# LEDChain1.net
KiCad netlist of a schematic drawn in Altium Designer
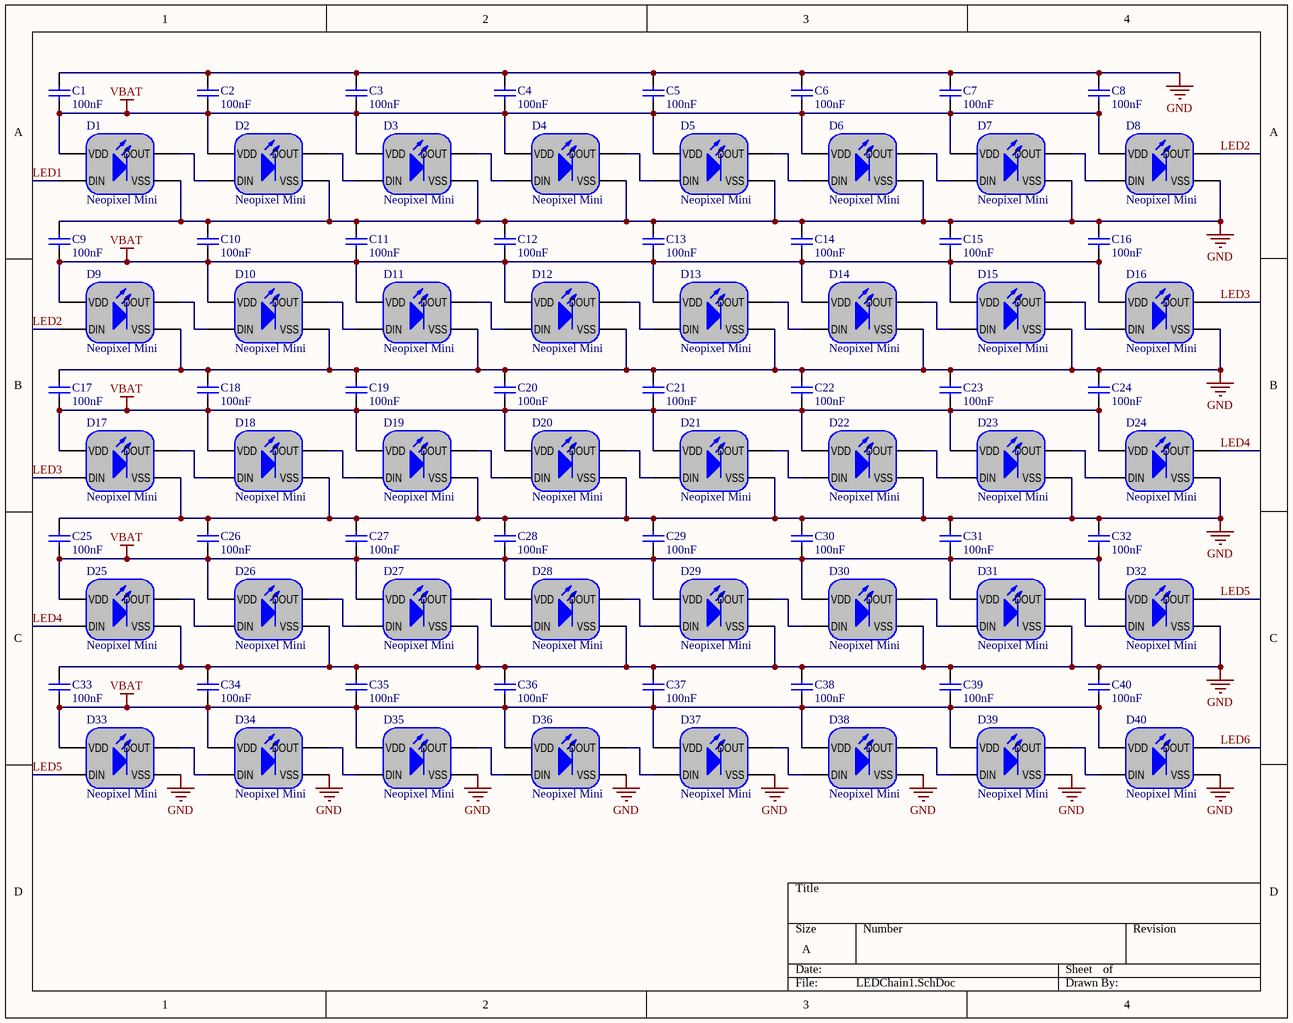
[diagram p0: LEDChain1.SchDoc]

(export (version "E")
  (design (tool "Eeschema 10.0.6"))
  (components
    (comp (ref "C1")
      (value "100nF")
      (footprint "0402_CAP")
      (description "CAP CER 0.1UF 16V X7R 0402")
      (fields (field (name "PUBLISHER") "Altium Limited"))
      (libsource (lib "Common Passives") (part "CAP_100N_0603"))
    )
    (comp (ref "C2")
      (value "100nF")
      (footprint "0402_CAP")
      (description "CAP CER 0.1UF 16V X7R 0402")
      (fields (field (name "PUBLISHER") "Altium Limited"))
      (libsource (lib "Common Passives") (part "CAP_100N_0603"))
    )
    (comp (ref "C3")
      (value "100nF")
      (footprint "0402_CAP")
      (description "CAP CER 0.1UF 16V X7R 0402")
      (fields (field (name "PUBLISHER") "Altium Limited"))
      (libsource (lib "Common Passives") (part "CAP_100N_0603"))
    )
    (comp (ref "C4")
      (value "100nF")
      (footprint "0402_CAP")
      (description "CAP CER 0.1UF 16V X7R 0402")
      (fields (field (name "PUBLISHER") "Altium Limited"))
      (libsource (lib "Common Passives") (part "CAP_100N_0603"))
    )
    (comp (ref "C5")
      (value "100nF")
      (footprint "0402_CAP")
      (description "CAP CER 0.1UF 16V X7R 0402")
      (fields (field (name "PUBLISHER") "Altium Limited"))
      (libsource (lib "Common Passives") (part "CAP_100N_0603"))
    )
    (comp (ref "C6")
      (value "100nF")
      (footprint "0402_CAP")
      (description "CAP CER 0.1UF 16V X7R 0402")
      (fields (field (name "PUBLISHER") "Altium Limited"))
      (libsource (lib "Common Passives") (part "CAP_100N_0603"))
    )
    (comp (ref "C7")
      (value "100nF")
      (footprint "0402_CAP")
      (description "CAP CER 0.1UF 16V X7R 0402")
      (fields (field (name "PUBLISHER") "Altium Limited"))
      (libsource (lib "Common Passives") (part "CAP_100N_0603"))
    )
    (comp (ref "C8")
      (value "100nF")
      (footprint "0402_CAP")
      (description "CAP CER 0.1UF 16V X7R 0402")
      (fields (field (name "PUBLISHER") "Altium Limited"))
      (libsource (lib "Common Passives") (part "CAP_100N_0603"))
    )
    (comp (ref "C9")
      (value "100nF")
      (footprint "0402_CAP")
      (description "CAP CER 0.1UF 16V X7R 0402")
      (fields (field (name "PUBLISHER") "Altium Limited"))
      (libsource (lib "Common Passives") (part "CAP_100N_0603"))
    )
    (comp (ref "C10")
      (value "100nF")
      (footprint "0402_CAP")
      (description "CAP CER 0.1UF 16V X7R 0402")
      (fields (field (name "PUBLISHER") "Altium Limited"))
      (libsource (lib "Common Passives") (part "CAP_100N_0603"))
    )
    (comp (ref "C11")
      (value "100nF")
      (footprint "0402_CAP")
      (description "CAP CER 0.1UF 16V X7R 0402")
      (fields (field (name "PUBLISHER") "Altium Limited"))
      (libsource (lib "Common Passives") (part "CAP_100N_0603"))
    )
    (comp (ref "C12")
      (value "100nF")
      (footprint "0402_CAP")
      (description "CAP CER 0.1UF 16V X7R 0402")
      (fields (field (name "PUBLISHER") "Altium Limited"))
      (libsource (lib "Common Passives") (part "CAP_100N_0603"))
    )
    (comp (ref "C13")
      (value "100nF")
      (footprint "0402_CAP")
      (description "CAP CER 0.1UF 16V X7R 0402")
      (fields (field (name "PUBLISHER") "Altium Limited"))
      (libsource (lib "Common Passives") (part "CAP_100N_0603"))
    )
    (comp (ref "C14")
      (value "100nF")
      (footprint "0402_CAP")
      (description "CAP CER 0.1UF 16V X7R 0402")
      (fields (field (name "PUBLISHER") "Altium Limited"))
      (libsource (lib "Common Passives") (part "CAP_100N_0603"))
    )
    (comp (ref "C15")
      (value "100nF")
      (footprint "0402_CAP")
      (description "CAP CER 0.1UF 16V X7R 0402")
      (fields (field (name "PUBLISHER") "Altium Limited"))
      (libsource (lib "Common Passives") (part "CAP_100N_0603"))
    )
    (comp (ref "C16")
      (value "100nF")
      (footprint "0402_CAP")
      (description "CAP CER 0.1UF 16V X7R 0402")
      (fields (field (name "PUBLISHER") "Altium Limited"))
      (libsource (lib "Common Passives") (part "CAP_100N_0603"))
    )
    (comp (ref "C17")
      (value "100nF")
      (footprint "0402_CAP")
      (description "CAP CER 0.1UF 16V X7R 0402")
      (fields (field (name "PUBLISHER") "Altium Limited"))
      (libsource (lib "Common Passives") (part "CAP_100N_0603"))
    )
    (comp (ref "C18")
      (value "100nF")
      (footprint "0402_CAP")
      (description "CAP CER 0.1UF 16V X7R 0402")
      (fields (field (name "PUBLISHER") "Altium Limited"))
      (libsource (lib "Common Passives") (part "CAP_100N_0603"))
    )
    (comp (ref "C19")
      (value "100nF")
      (footprint "0402_CAP")
      (description "CAP CER 0.1UF 16V X7R 0402")
      (fields (field (name "PUBLISHER") "Altium Limited"))
      (libsource (lib "Common Passives") (part "CAP_100N_0603"))
    )
    (comp (ref "C20")
      (value "100nF")
      (footprint "0402_CAP")
      (description "CAP CER 0.1UF 16V X7R 0402")
      (fields (field (name "PUBLISHER") "Altium Limited"))
      (libsource (lib "Common Passives") (part "CAP_100N_0603"))
    )
    (comp (ref "C21")
      (value "100nF")
      (footprint "0402_CAP")
      (description "CAP CER 0.1UF 16V X7R 0402")
      (fields (field (name "PUBLISHER") "Altium Limited"))
      (libsource (lib "Common Passives") (part "CAP_100N_0603"))
    )
    (comp (ref "C22")
      (value "100nF")
      (footprint "0402_CAP")
      (description "CAP CER 0.1UF 16V X7R 0402")
      (fields (field (name "PUBLISHER") "Altium Limited"))
      (libsource (lib "Common Passives") (part "CAP_100N_0603"))
    )
    (comp (ref "C23")
      (value "100nF")
      (footprint "0402_CAP")
      (description "CAP CER 0.1UF 16V X7R 0402")
      (fields (field (name "PUBLISHER") "Altium Limited"))
      (libsource (lib "Common Passives") (part "CAP_100N_0603"))
    )
    (comp (ref "C24")
      (value "100nF")
      (footprint "0402_CAP")
      (description "CAP CER 0.1UF 16V X7R 0402")
      (fields (field (name "PUBLISHER") "Altium Limited"))
      (libsource (lib "Common Passives") (part "CAP_100N_0603"))
    )
    (comp (ref "C25")
      (value "100nF")
      (footprint "0402_CAP")
      (description "CAP CER 0.1UF 16V X7R 0402")
      (fields (field (name "PUBLISHER") "Altium Limited"))
      (libsource (lib "Common Passives") (part "CAP_100N_0603"))
    )
    (comp (ref "C26")
      (value "100nF")
      (footprint "0402_CAP")
      (description "CAP CER 0.1UF 16V X7R 0402")
      (fields (field (name "PUBLISHER") "Altium Limited"))
      (libsource (lib "Common Passives") (part "CAP_100N_0603"))
    )
    (comp (ref "C27")
      (value "100nF")
      (footprint "0402_CAP")
      (description "CAP CER 0.1UF 16V X7R 0402")
      (fields (field (name "PUBLISHER") "Altium Limited"))
      (libsource (lib "Common Passives") (part "CAP_100N_0603"))
    )
    (comp (ref "C28")
      (value "100nF")
      (footprint "0402_CAP")
      (description "CAP CER 0.1UF 16V X7R 0402")
      (fields (field (name "PUBLISHER") "Altium Limited"))
      (libsource (lib "Common Passives") (part "CAP_100N_0603"))
    )
    (comp (ref "C29")
      (value "100nF")
      (footprint "0402_CAP")
      (description "CAP CER 0.1UF 16V X7R 0402")
      (fields (field (name "PUBLISHER") "Altium Limited"))
      (libsource (lib "Common Passives") (part "CAP_100N_0603"))
    )
    (comp (ref "C30")
      (value "100nF")
      (footprint "0402_CAP")
      (description "CAP CER 0.1UF 16V X7R 0402")
      (fields (field (name "PUBLISHER") "Altium Limited"))
      (libsource (lib "Common Passives") (part "CAP_100N_0603"))
    )
    (comp (ref "C31")
      (value "100nF")
      (footprint "0402_CAP")
      (description "CAP CER 0.1UF 16V X7R 0402")
      (fields (field (name "PUBLISHER") "Altium Limited"))
      (libsource (lib "Common Passives") (part "CAP_100N_0603"))
    )
    (comp (ref "C32")
      (value "100nF")
      (footprint "0402_CAP")
      (description "CAP CER 0.1UF 16V X7R 0402")
      (fields (field (name "PUBLISHER") "Altium Limited"))
      (libsource (lib "Common Passives") (part "CAP_100N_0603"))
    )
    (comp (ref "C33")
      (value "100nF")
      (footprint "0402_CAP")
      (description "CAP CER 0.1UF 16V X7R 0402")
      (fields (field (name "PUBLISHER") "Altium Limited"))
      (libsource (lib "Common Passives") (part "CAP_100N_0603"))
    )
    (comp (ref "C34")
      (value "100nF")
      (footprint "0402_CAP")
      (description "CAP CER 0.1UF 16V X7R 0402")
      (fields (field (name "PUBLISHER") "Altium Limited"))
      (libsource (lib "Common Passives") (part "CAP_100N_0603"))
    )
    (comp (ref "C35")
      (value "100nF")
      (footprint "0402_CAP")
      (description "CAP CER 0.1UF 16V X7R 0402")
      (fields (field (name "PUBLISHER") "Altium Limited"))
      (libsource (lib "Common Passives") (part "CAP_100N_0603"))
    )
    (comp (ref "C36")
      (value "100nF")
      (footprint "0402_CAP")
      (description "CAP CER 0.1UF 16V X7R 0402")
      (fields (field (name "PUBLISHER") "Altium Limited"))
      (libsource (lib "Common Passives") (part "CAP_100N_0603"))
    )
    (comp (ref "C37")
      (value "100nF")
      (footprint "0402_CAP")
      (description "CAP CER 0.1UF 16V X7R 0402")
      (fields (field (name "PUBLISHER") "Altium Limited"))
      (libsource (lib "Common Passives") (part "CAP_100N_0603"))
    )
    (comp (ref "C38")
      (value "100nF")
      (footprint "0402_CAP")
      (description "CAP CER 0.1UF 16V X7R 0402")
      (fields (field (name "PUBLISHER") "Altium Limited"))
      (libsource (lib "Common Passives") (part "CAP_100N_0603"))
    )
    (comp (ref "C39")
      (value "100nF")
      (footprint "0402_CAP")
      (description "CAP CER 0.1UF 16V X7R 0402")
      (fields (field (name "PUBLISHER") "Altium Limited"))
      (libsource (lib "Common Passives") (part "CAP_100N_0603"))
    )
    (comp (ref "C40")
      (value "100nF")
      (footprint "0402_CAP")
      (description "CAP CER 0.1UF 16V X7R 0402")
      (fields (field (name "PUBLISHER") "Altium Limited"))
      (libsource (lib "Common Passives") (part "CAP_100N_0603"))
    )
    (comp (ref "D1")
      (value "Neopixel Mini")
      (footprint "SK6812 (3535)")
      (description "ADDRESS LED DISC SERIAL RGB")
      (libsource (lib "Diodes") (part "SK6812MINI-B-001"))
    )
    (comp (ref "D2")
      (value "Neopixel Mini")
      (footprint "SK6812 (3535)")
      (description "ADDRESS LED DISC SERIAL RGB")
      (libsource (lib "Diodes") (part "SK6812MINI-B-001"))
    )
    (comp (ref "D3")
      (value "Neopixel Mini")
      (footprint "SK6812 (3535)")
      (description "ADDRESS LED DISC SERIAL RGB")
      (libsource (lib "Diodes") (part "SK6812MINI-B-001"))
    )
    (comp (ref "D4")
      (value "Neopixel Mini")
      (footprint "SK6812 (3535)")
      (description "ADDRESS LED DISC SERIAL RGB")
      (libsource (lib "Diodes") (part "SK6812MINI-B-001"))
    )
    (comp (ref "D5")
      (value "Neopixel Mini")
      (footprint "SK6812 (3535)")
      (description "ADDRESS LED DISC SERIAL RGB")
      (libsource (lib "Diodes") (part "SK6812MINI-B-001"))
    )
    (comp (ref "D6")
      (value "Neopixel Mini")
      (footprint "SK6812 (3535)")
      (description "ADDRESS LED DISC SERIAL RGB")
      (libsource (lib "Diodes") (part "SK6812MINI-B-001"))
    )
    (comp (ref "D7")
      (value "Neopixel Mini")
      (footprint "SK6812 (3535)")
      (description "ADDRESS LED DISC SERIAL RGB")
      (libsource (lib "Diodes") (part "SK6812MINI-B-001"))
    )
    (comp (ref "D8")
      (value "Neopixel Mini")
      (footprint "SK6812 (3535)")
      (description "ADDRESS LED DISC SERIAL RGB")
      (libsource (lib "Diodes") (part "SK6812MINI-B-001"))
    )
    (comp (ref "D9")
      (value "Neopixel Mini")
      (footprint "SK6812 (3535)")
      (description "ADDRESS LED DISC SERIAL RGB")
      (libsource (lib "Diodes") (part "SK6812MINI-B-001"))
    )
    (comp (ref "D10")
      (value "Neopixel Mini")
      (footprint "SK6812 (3535)")
      (description "ADDRESS LED DISC SERIAL RGB")
      (libsource (lib "Diodes") (part "SK6812MINI-B-001"))
    )
    (comp (ref "D11")
      (value "Neopixel Mini")
      (footprint "SK6812 (3535)")
      (description "ADDRESS LED DISC SERIAL RGB")
      (libsource (lib "Diodes") (part "SK6812MINI-B-001"))
    )
    (comp (ref "D12")
      (value "Neopixel Mini")
      (footprint "SK6812 (3535)")
      (description "ADDRESS LED DISC SERIAL RGB")
      (libsource (lib "Diodes") (part "SK6812MINI-B-001"))
    )
    (comp (ref "D13")
      (value "Neopixel Mini")
      (footprint "SK6812 (3535)")
      (description "ADDRESS LED DISC SERIAL RGB")
      (libsource (lib "Diodes") (part "SK6812MINI-B-001"))
    )
    (comp (ref "D14")
      (value "Neopixel Mini")
      (footprint "SK6812 (3535)")
      (description "ADDRESS LED DISC SERIAL RGB")
      (libsource (lib "Diodes") (part "SK6812MINI-B-001"))
    )
    (comp (ref "D15")
      (value "Neopixel Mini")
      (footprint "SK6812 (3535)")
      (description "ADDRESS LED DISC SERIAL RGB")
      (libsource (lib "Diodes") (part "SK6812MINI-B-001"))
    )
    (comp (ref "D16")
      (value "Neopixel Mini")
      (footprint "SK6812 (3535)")
      (description "ADDRESS LED DISC SERIAL RGB")
      (libsource (lib "Diodes") (part "SK6812MINI-B-001"))
    )
    (comp (ref "D17")
      (value "Neopixel Mini")
      (footprint "SK6812 (3535)")
      (description "ADDRESS LED DISC SERIAL RGB")
      (libsource (lib "Diodes") (part "SK6812MINI-B-001"))
    )
    (comp (ref "D18")
      (value "Neopixel Mini")
      (footprint "SK6812 (3535)")
      (description "ADDRESS LED DISC SERIAL RGB")
      (libsource (lib "Diodes") (part "SK6812MINI-B-001"))
    )
    (comp (ref "D19")
      (value "Neopixel Mini")
      (footprint "SK6812 (3535)")
      (description "ADDRESS LED DISC SERIAL RGB")
      (libsource (lib "Diodes") (part "SK6812MINI-B-001"))
    )
    (comp (ref "D20")
      (value "Neopixel Mini")
      (footprint "SK6812 (3535)")
      (description "ADDRESS LED DISC SERIAL RGB")
      (libsource (lib "Diodes") (part "SK6812MINI-B-001"))
    )
    (comp (ref "D21")
      (value "Neopixel Mini")
      (footprint "SK6812 (3535)")
      (description "ADDRESS LED DISC SERIAL RGB")
      (libsource (lib "Diodes") (part "SK6812MINI-B-001"))
    )
    (comp (ref "D22")
      (value "Neopixel Mini")
      (footprint "SK6812 (3535)")
      (description "ADDRESS LED DISC SERIAL RGB")
      (libsource (lib "Diodes") (part "SK6812MINI-B-001"))
    )
    (comp (ref "D23")
      (value "Neopixel Mini")
      (footprint "SK6812 (3535)")
      (description "ADDRESS LED DISC SERIAL RGB")
      (libsource (lib "Diodes") (part "SK6812MINI-B-001"))
    )
    (comp (ref "D24")
      (value "Neopixel Mini")
      (footprint "SK6812 (3535)")
      (description "ADDRESS LED DISC SERIAL RGB")
      (libsource (lib "Diodes") (part "SK6812MINI-B-001"))
    )
    (comp (ref "D25")
      (value "Neopixel Mini")
      (footprint "SK6812 (3535)")
      (description "ADDRESS LED DISC SERIAL RGB")
      (libsource (lib "Diodes") (part "SK6812MINI-B-001"))
    )
    (comp (ref "D26")
      (value "Neopixel Mini")
      (footprint "SK6812 (3535)")
      (description "ADDRESS LED DISC SERIAL RGB")
      (libsource (lib "Diodes") (part "SK6812MINI-B-001"))
    )
    (comp (ref "D27")
      (value "Neopixel Mini")
      (footprint "SK6812 (3535)")
      (description "ADDRESS LED DISC SERIAL RGB")
      (libsource (lib "Diodes") (part "SK6812MINI-B-001"))
    )
    (comp (ref "D28")
      (value "Neopixel Mini")
      (footprint "SK6812 (3535)")
      (description "ADDRESS LED DISC SERIAL RGB")
      (libsource (lib "Diodes") (part "SK6812MINI-B-001"))
    )
    (comp (ref "D29")
      (value "Neopixel Mini")
      (footprint "SK6812 (3535)")
      (description "ADDRESS LED DISC SERIAL RGB")
      (libsource (lib "Diodes") (part "SK6812MINI-B-001"))
    )
    (comp (ref "D30")
      (value "Neopixel Mini")
      (footprint "SK6812 (3535)")
      (description "ADDRESS LED DISC SERIAL RGB")
      (libsource (lib "Diodes") (part "SK6812MINI-B-001"))
    )
    (comp (ref "D31")
      (value "Neopixel Mini")
      (footprint "SK6812 (3535)")
      (description "ADDRESS LED DISC SERIAL RGB")
      (libsource (lib "Diodes") (part "SK6812MINI-B-001"))
    )
    (comp (ref "D32")
      (value "Neopixel Mini")
      (footprint "SK6812 (3535)")
      (description "ADDRESS LED DISC SERIAL RGB")
      (libsource (lib "Diodes") (part "SK6812MINI-B-001"))
    )
    (comp (ref "D33")
      (value "Neopixel Mini")
      (footprint "SK6812 (3535)")
      (description "ADDRESS LED DISC SERIAL RGB")
      (libsource (lib "Diodes") (part "SK6812MINI-B-001"))
    )
    (comp (ref "D34")
      (value "Neopixel Mini")
      (footprint "SK6812 (3535)")
      (description "ADDRESS LED DISC SERIAL RGB")
      (libsource (lib "Diodes") (part "SK6812MINI-B-001"))
    )
    (comp (ref "D35")
      (value "Neopixel Mini")
      (footprint "SK6812 (3535)")
      (description "ADDRESS LED DISC SERIAL RGB")
      (libsource (lib "Diodes") (part "SK6812MINI-B-001"))
    )
    (comp (ref "D36")
      (value "Neopixel Mini")
      (footprint "SK6812 (3535)")
      (description "ADDRESS LED DISC SERIAL RGB")
      (libsource (lib "Diodes") (part "SK6812MINI-B-001"))
    )
    (comp (ref "D37")
      (value "Neopixel Mini")
      (footprint "SK6812 (3535)")
      (description "ADDRESS LED DISC SERIAL RGB")
      (libsource (lib "Diodes") (part "SK6812MINI-B-001"))
    )
    (comp (ref "D38")
      (value "Neopixel Mini")
      (footprint "SK6812 (3535)")
      (description "ADDRESS LED DISC SERIAL RGB")
      (libsource (lib "Diodes") (part "SK6812MINI-B-001"))
    )
    (comp (ref "D39")
      (value "Neopixel Mini")
      (footprint "SK6812 (3535)")
      (description "ADDRESS LED DISC SERIAL RGB")
      (libsource (lib "Diodes") (part "SK6812MINI-B-001"))
    )
    (comp (ref "D40")
      (value "Neopixel Mini")
      (footprint "SK6812 (3535)")
      (description "ADDRESS LED DISC SERIAL RGB")
      (libsource (lib "Diodes") (part "SK6812MINI-B-001"))
    )
  )
  (nets
    (net (code "1") (name "/LED1") (class "Default")
      (node (ref "D1") (pin "3") (pinfunction "DIN_3") (pintype "passive"))
    )
    (net (code "2") (name "/LED2") (class "Default")
      (node (ref "D8") (pin "1") (pinfunction "DOUT_1") (pintype "passive"))
      (node (ref "D9") (pin "3") (pinfunction "DIN_3") (pintype "passive"))
    )
    (net (code "3") (name "/LED3") (class "Default")
      (node (ref "D16") (pin "1") (pinfunction "DOUT_1") (pintype "passive"))
      (node (ref "D17") (pin "3") (pinfunction "DIN_3") (pintype "passive"))
    )
    (net (code "4") (name "/LED4") (class "Default")
      (node (ref "D24") (pin "1") (pinfunction "DOUT_1") (pintype "passive"))
      (node (ref "D25") (pin "3") (pinfunction "DIN_3") (pintype "passive"))
    )
    (net (code "5") (name "/LED5") (class "Default")
      (node (ref "D32") (pin "1") (pinfunction "DOUT_1") (pintype "passive"))
      (node (ref "D33") (pin "3") (pinfunction "DIN_3") (pintype "passive"))
    )
    (net (code "6") (name "/LED6") (class "Default")
      (node (ref "D40") (pin "1") (pinfunction "DOUT_1") (pintype "passive"))
    )
    (net (code "7") (name "GND") (class "Default")
      (node (ref "C1") (pin "2") (pinfunction "2_2") (pintype "passive"))
      (node (ref "C10") (pin "2") (pinfunction "2_2") (pintype "passive"))
      (node (ref "C11") (pin "2") (pinfunction "2_2") (pintype "passive"))
      (node (ref "C12") (pin "2") (pinfunction "2_2") (pintype "passive"))
      (node (ref "C13") (pin "2") (pinfunction "2_2") (pintype "passive"))
      (node (ref "C14") (pin "2") (pinfunction "2_2") (pintype "passive"))
      (node (ref "C15") (pin "2") (pinfunction "2_2") (pintype "passive"))
      (node (ref "C16") (pin "2") (pinfunction "2_2") (pintype "passive"))
      (node (ref "C17") (pin "2") (pinfunction "2_2") (pintype "passive"))
      (node (ref "C18") (pin "2") (pinfunction "2_2") (pintype "passive"))
      (node (ref "C19") (pin "2") (pinfunction "2_2") (pintype "passive"))
      (node (ref "C2") (pin "2") (pinfunction "2_2") (pintype "passive"))
      (node (ref "C20") (pin "2") (pinfunction "2_2") (pintype "passive"))
      (node (ref "C21") (pin "2") (pinfunction "2_2") (pintype "passive"))
      (node (ref "C22") (pin "2") (pinfunction "2_2") (pintype "passive"))
      (node (ref "C23") (pin "2") (pinfunction "2_2") (pintype "passive"))
      (node (ref "C24") (pin "2") (pinfunction "2_2") (pintype "passive"))
      (node (ref "C25") (pin "2") (pinfunction "2_2") (pintype "passive"))
      (node (ref "C26") (pin "2") (pinfunction "2_2") (pintype "passive"))
      (node (ref "C27") (pin "2") (pinfunction "2_2") (pintype "passive"))
      (node (ref "C28") (pin "2") (pinfunction "2_2") (pintype "passive"))
      (node (ref "C29") (pin "2") (pinfunction "2_2") (pintype "passive"))
      (node (ref "C3") (pin "2") (pinfunction "2_2") (pintype "passive"))
      (node (ref "C30") (pin "2") (pinfunction "2_2") (pintype "passive"))
      (node (ref "C31") (pin "2") (pinfunction "2_2") (pintype "passive"))
      (node (ref "C32") (pin "2") (pinfunction "2_2") (pintype "passive"))
      (node (ref "C33") (pin "2") (pinfunction "2_2") (pintype "passive"))
      (node (ref "C34") (pin "2") (pinfunction "2_2") (pintype "passive"))
      (node (ref "C35") (pin "2") (pinfunction "2_2") (pintype "passive"))
      (node (ref "C36") (pin "2") (pinfunction "2_2") (pintype "passive"))
      (node (ref "C37") (pin "2") (pinfunction "2_2") (pintype "passive"))
      (node (ref "C38") (pin "2") (pinfunction "2_2") (pintype "passive"))
      (node (ref "C39") (pin "2") (pinfunction "2_2") (pintype "passive"))
      (node (ref "C4") (pin "2") (pinfunction "2_2") (pintype "passive"))
      (node (ref "C40") (pin "2") (pinfunction "2_2") (pintype "passive"))
      (node (ref "C5") (pin "2") (pinfunction "2_2") (pintype "passive"))
      (node (ref "C6") (pin "2") (pinfunction "2_2") (pintype "passive"))
      (node (ref "C7") (pin "2") (pinfunction "2_2") (pintype "passive"))
      (node (ref "C8") (pin "2") (pinfunction "2_2") (pintype "passive"))
      (node (ref "C9") (pin "2") (pinfunction "2_2") (pintype "passive"))
      (node (ref "D1") (pin "2") (pinfunction "VSS_2") (pintype "passive"))
      (node (ref "D10") (pin "2") (pinfunction "VSS_2") (pintype "passive"))
      (node (ref "D11") (pin "2") (pinfunction "VSS_2") (pintype "passive"))
      (node (ref "D12") (pin "2") (pinfunction "VSS_2") (pintype "passive"))
      (node (ref "D13") (pin "2") (pinfunction "VSS_2") (pintype "passive"))
      (node (ref "D14") (pin "2") (pinfunction "VSS_2") (pintype "passive"))
      (node (ref "D15") (pin "2") (pinfunction "VSS_2") (pintype "passive"))
      (node (ref "D16") (pin "2") (pinfunction "VSS_2") (pintype "passive"))
      (node (ref "D17") (pin "2") (pinfunction "VSS_2") (pintype "passive"))
      (node (ref "D18") (pin "2") (pinfunction "VSS_2") (pintype "passive"))
      (node (ref "D19") (pin "2") (pinfunction "VSS_2") (pintype "passive"))
      (node (ref "D2") (pin "2") (pinfunction "VSS_2") (pintype "passive"))
      (node (ref "D20") (pin "2") (pinfunction "VSS_2") (pintype "passive"))
      (node (ref "D21") (pin "2") (pinfunction "VSS_2") (pintype "passive"))
      (node (ref "D22") (pin "2") (pinfunction "VSS_2") (pintype "passive"))
      (node (ref "D23") (pin "2") (pinfunction "VSS_2") (pintype "passive"))
      (node (ref "D24") (pin "2") (pinfunction "VSS_2") (pintype "passive"))
      (node (ref "D25") (pin "2") (pinfunction "VSS_2") (pintype "passive"))
      (node (ref "D26") (pin "2") (pinfunction "VSS_2") (pintype "passive"))
      (node (ref "D27") (pin "2") (pinfunction "VSS_2") (pintype "passive"))
      (node (ref "D28") (pin "2") (pinfunction "VSS_2") (pintype "passive"))
      (node (ref "D29") (pin "2") (pinfunction "VSS_2") (pintype "passive"))
      (node (ref "D3") (pin "2") (pinfunction "VSS_2") (pintype "passive"))
      (node (ref "D30") (pin "2") (pinfunction "VSS_2") (pintype "passive"))
      (node (ref "D31") (pin "2") (pinfunction "VSS_2") (pintype "passive"))
      (node (ref "D32") (pin "2") (pinfunction "VSS_2") (pintype "passive"))
      (node (ref "D33") (pin "2") (pinfunction "VSS_2") (pintype "passive"))
      (node (ref "D34") (pin "2") (pinfunction "VSS_2") (pintype "passive"))
      (node (ref "D35") (pin "2") (pinfunction "VSS_2") (pintype "passive"))
      (node (ref "D36") (pin "2") (pinfunction "VSS_2") (pintype "passive"))
      (node (ref "D37") (pin "2") (pinfunction "VSS_2") (pintype "passive"))
      (node (ref "D38") (pin "2") (pinfunction "VSS_2") (pintype "passive"))
      (node (ref "D39") (pin "2") (pinfunction "VSS_2") (pintype "passive"))
      (node (ref "D4") (pin "2") (pinfunction "VSS_2") (pintype "passive"))
      (node (ref "D40") (pin "2") (pinfunction "VSS_2") (pintype "passive"))
      (node (ref "D5") (pin "2") (pinfunction "VSS_2") (pintype "passive"))
      (node (ref "D6") (pin "2") (pinfunction "VSS_2") (pintype "passive"))
      (node (ref "D7") (pin "2") (pinfunction "VSS_2") (pintype "passive"))
      (node (ref "D8") (pin "2") (pinfunction "VSS_2") (pintype "passive"))
      (node (ref "D9") (pin "2") (pinfunction "VSS_2") (pintype "passive"))
    )
    (net (code "8") (name "Net-(D1-DOUT)") (class "Default")
      (node (ref "D1") (pin "1") (pinfunction "DOUT_1") (pintype "passive"))
      (node (ref "D2") (pin "3") (pinfunction "DIN_3") (pintype "passive"))
    )
    (net (code "9") (name "Net-(D2-DOUT)") (class "Default")
      (node (ref "D2") (pin "1") (pinfunction "DOUT_1") (pintype "passive"))
      (node (ref "D3") (pin "3") (pinfunction "DIN_3") (pintype "passive"))
    )
    (net (code "10") (name "Net-(D3-DOUT)") (class "Default")
      (node (ref "D3") (pin "1") (pinfunction "DOUT_1") (pintype "passive"))
      (node (ref "D4") (pin "3") (pinfunction "DIN_3") (pintype "passive"))
    )
    (net (code "11") (name "Net-(D4-DOUT)") (class "Default")
      (node (ref "D4") (pin "1") (pinfunction "DOUT_1") (pintype "passive"))
      (node (ref "D5") (pin "3") (pinfunction "DIN_3") (pintype "passive"))
    )
    (net (code "12") (name "Net-(D5-DOUT)") (class "Default")
      (node (ref "D5") (pin "1") (pinfunction "DOUT_1") (pintype "passive"))
      (node (ref "D6") (pin "3") (pinfunction "DIN_3") (pintype "passive"))
    )
    (net (code "13") (name "Net-(D6-DOUT)") (class "Default")
      (node (ref "D6") (pin "1") (pinfunction "DOUT_1") (pintype "passive"))
      (node (ref "D7") (pin "3") (pinfunction "DIN_3") (pintype "passive"))
    )
    (net (code "14") (name "Net-(D7-DOUT)") (class "Default")
      (node (ref "D7") (pin "1") (pinfunction "DOUT_1") (pintype "passive"))
      (node (ref "D8") (pin "3") (pinfunction "DIN_3") (pintype "passive"))
    )
    (net (code "15") (name "Net-(D10-DIN)") (class "Default")
      (node (ref "D10") (pin "3") (pinfunction "DIN_3") (pintype "passive"))
      (node (ref "D9") (pin "1") (pinfunction "DOUT_1") (pintype "passive"))
    )
    (net (code "16") (name "Net-(D10-DOUT)") (class "Default")
      (node (ref "D10") (pin "1") (pinfunction "DOUT_1") (pintype "passive"))
      (node (ref "D11") (pin "3") (pinfunction "DIN_3") (pintype "passive"))
    )
    (net (code "17") (name "Net-(D11-DOUT)") (class "Default")
      (node (ref "D11") (pin "1") (pinfunction "DOUT_1") (pintype "passive"))
      (node (ref "D12") (pin "3") (pinfunction "DIN_3") (pintype "passive"))
    )
    (net (code "18") (name "Net-(D12-DOUT)") (class "Default")
      (node (ref "D12") (pin "1") (pinfunction "DOUT_1") (pintype "passive"))
      (node (ref "D13") (pin "3") (pinfunction "DIN_3") (pintype "passive"))
    )
    (net (code "19") (name "Net-(D13-DOUT)") (class "Default")
      (node (ref "D13") (pin "1") (pinfunction "DOUT_1") (pintype "passive"))
      (node (ref "D14") (pin "3") (pinfunction "DIN_3") (pintype "passive"))
    )
    (net (code "20") (name "Net-(D14-DOUT)") (class "Default")
      (node (ref "D14") (pin "1") (pinfunction "DOUT_1") (pintype "passive"))
      (node (ref "D15") (pin "3") (pinfunction "DIN_3") (pintype "passive"))
    )
    (net (code "21") (name "Net-(D15-DOUT)") (class "Default")
      (node (ref "D15") (pin "1") (pinfunction "DOUT_1") (pintype "passive"))
      (node (ref "D16") (pin "3") (pinfunction "DIN_3") (pintype "passive"))
    )
    (net (code "22") (name "Net-(D17-DOUT)") (class "Default")
      (node (ref "D17") (pin "1") (pinfunction "DOUT_1") (pintype "passive"))
      (node (ref "D18") (pin "3") (pinfunction "DIN_3") (pintype "passive"))
    )
    (net (code "23") (name "Net-(D18-DOUT)") (class "Default")
      (node (ref "D18") (pin "1") (pinfunction "DOUT_1") (pintype "passive"))
      (node (ref "D19") (pin "3") (pinfunction "DIN_3") (pintype "passive"))
    )
    (net (code "24") (name "Net-(D19-DOUT)") (class "Default")
      (node (ref "D19") (pin "1") (pinfunction "DOUT_1") (pintype "passive"))
      (node (ref "D20") (pin "3") (pinfunction "DIN_3") (pintype "passive"))
    )
    (net (code "25") (name "Net-(D20-DOUT)") (class "Default")
      (node (ref "D20") (pin "1") (pinfunction "DOUT_1") (pintype "passive"))
      (node (ref "D21") (pin "3") (pinfunction "DIN_3") (pintype "passive"))
    )
    (net (code "26") (name "Net-(D21-DOUT)") (class "Default")
      (node (ref "D21") (pin "1") (pinfunction "DOUT_1") (pintype "passive"))
      (node (ref "D22") (pin "3") (pinfunction "DIN_3") (pintype "passive"))
    )
    (net (code "27") (name "Net-(D22-DOUT)") (class "Default")
      (node (ref "D22") (pin "1") (pinfunction "DOUT_1") (pintype "passive"))
      (node (ref "D23") (pin "3") (pinfunction "DIN_3") (pintype "passive"))
    )
    (net (code "28") (name "Net-(D23-DOUT)") (class "Default")
      (node (ref "D23") (pin "1") (pinfunction "DOUT_1") (pintype "passive"))
      (node (ref "D24") (pin "3") (pinfunction "DIN_3") (pintype "passive"))
    )
    (net (code "29") (name "Net-(D25-DOUT)") (class "Default")
      (node (ref "D25") (pin "1") (pinfunction "DOUT_1") (pintype "passive"))
      (node (ref "D26") (pin "3") (pinfunction "DIN_3") (pintype "passive"))
    )
    (net (code "30") (name "Net-(D26-DOUT)") (class "Default")
      (node (ref "D26") (pin "1") (pinfunction "DOUT_1") (pintype "passive"))
      (node (ref "D27") (pin "3") (pinfunction "DIN_3") (pintype "passive"))
    )
    (net (code "31") (name "Net-(D27-DOUT)") (class "Default")
      (node (ref "D27") (pin "1") (pinfunction "DOUT_1") (pintype "passive"))
      (node (ref "D28") (pin "3") (pinfunction "DIN_3") (pintype "passive"))
    )
    (net (code "32") (name "Net-(D28-DOUT)") (class "Default")
      (node (ref "D28") (pin "1") (pinfunction "DOUT_1") (pintype "passive"))
      (node (ref "D29") (pin "3") (pinfunction "DIN_3") (pintype "passive"))
    )
    (net (code "33") (name "Net-(D29-DOUT)") (class "Default")
      (node (ref "D29") (pin "1") (pinfunction "DOUT_1") (pintype "passive"))
      (node (ref "D30") (pin "3") (pinfunction "DIN_3") (pintype "passive"))
    )
    (net (code "34") (name "Net-(D30-DOUT)") (class "Default")
      (node (ref "D30") (pin "1") (pinfunction "DOUT_1") (pintype "passive"))
      (node (ref "D31") (pin "3") (pinfunction "DIN_3") (pintype "passive"))
    )
    (net (code "35") (name "Net-(D31-DOUT)") (class "Default")
      (node (ref "D31") (pin "1") (pinfunction "DOUT_1") (pintype "passive"))
      (node (ref "D32") (pin "3") (pinfunction "DIN_3") (pintype "passive"))
    )
    (net (code "36") (name "Net-(D33-DOUT)") (class "Default")
      (node (ref "D33") (pin "1") (pinfunction "DOUT_1") (pintype "passive"))
      (node (ref "D34") (pin "3") (pinfunction "DIN_3") (pintype "passive"))
    )
    (net (code "37") (name "Net-(D34-DOUT)") (class "Default")
      (node (ref "D34") (pin "1") (pinfunction "DOUT_1") (pintype "passive"))
      (node (ref "D35") (pin "3") (pinfunction "DIN_3") (pintype "passive"))
    )
    (net (code "38") (name "Net-(D35-DOUT)") (class "Default")
      (node (ref "D35") (pin "1") (pinfunction "DOUT_1") (pintype "passive"))
      (node (ref "D36") (pin "3") (pinfunction "DIN_3") (pintype "passive"))
    )
    (net (code "39") (name "Net-(D36-DOUT)") (class "Default")
      (node (ref "D36") (pin "1") (pinfunction "DOUT_1") (pintype "passive"))
      (node (ref "D37") (pin "3") (pinfunction "DIN_3") (pintype "passive"))
    )
    (net (code "40") (name "Net-(D37-DOUT)") (class "Default")
      (node (ref "D37") (pin "1") (pinfunction "DOUT_1") (pintype "passive"))
      (node (ref "D38") (pin "3") (pinfunction "DIN_3") (pintype "passive"))
    )
    (net (code "41") (name "Net-(D38-DOUT)") (class "Default")
      (node (ref "D38") (pin "1") (pinfunction "DOUT_1") (pintype "passive"))
      (node (ref "D39") (pin "3") (pinfunction "DIN_3") (pintype "passive"))
    )
    (net (code "42") (name "Net-(D39-DOUT)") (class "Default")
      (node (ref "D39") (pin "1") (pinfunction "DOUT_1") (pintype "passive"))
      (node (ref "D40") (pin "3") (pinfunction "DIN_3") (pintype "passive"))
    )
    (net (code "43") (name "VBAT") (class "Default")
      (node (ref "C1") (pin "1") (pinfunction "1_1") (pintype "passive"))
      (node (ref "C10") (pin "1") (pinfunction "1_1") (pintype "passive"))
      (node (ref "C11") (pin "1") (pinfunction "1_1") (pintype "passive"))
      (node (ref "C12") (pin "1") (pinfunction "1_1") (pintype "passive"))
      (node (ref "C13") (pin "1") (pinfunction "1_1") (pintype "passive"))
      (node (ref "C14") (pin "1") (pinfunction "1_1") (pintype "passive"))
      (node (ref "C15") (pin "1") (pinfunction "1_1") (pintype "passive"))
      (node (ref "C16") (pin "1") (pinfunction "1_1") (pintype "passive"))
      (node (ref "C17") (pin "1") (pinfunction "1_1") (pintype "passive"))
      (node (ref "C18") (pin "1") (pinfunction "1_1") (pintype "passive"))
      (node (ref "C19") (pin "1") (pinfunction "1_1") (pintype "passive"))
      (node (ref "C2") (pin "1") (pinfunction "1_1") (pintype "passive"))
      (node (ref "C20") (pin "1") (pinfunction "1_1") (pintype "passive"))
      (node (ref "C21") (pin "1") (pinfunction "1_1") (pintype "passive"))
      (node (ref "C22") (pin "1") (pinfunction "1_1") (pintype "passive"))
      (node (ref "C23") (pin "1") (pinfunction "1_1") (pintype "passive"))
      (node (ref "C24") (pin "1") (pinfunction "1_1") (pintype "passive"))
      (node (ref "C25") (pin "1") (pinfunction "1_1") (pintype "passive"))
      (node (ref "C26") (pin "1") (pinfunction "1_1") (pintype "passive"))
      (node (ref "C27") (pin "1") (pinfunction "1_1") (pintype "passive"))
      (node (ref "C28") (pin "1") (pinfunction "1_1") (pintype "passive"))
      (node (ref "C29") (pin "1") (pinfunction "1_1") (pintype "passive"))
      (node (ref "C3") (pin "1") (pinfunction "1_1") (pintype "passive"))
      (node (ref "C30") (pin "1") (pinfunction "1_1") (pintype "passive"))
      (node (ref "C31") (pin "1") (pinfunction "1_1") (pintype "passive"))
      (node (ref "C32") (pin "1") (pinfunction "1_1") (pintype "passive"))
      (node (ref "C33") (pin "1") (pinfunction "1_1") (pintype "passive"))
      (node (ref "C34") (pin "1") (pinfunction "1_1") (pintype "passive"))
      (node (ref "C35") (pin "1") (pinfunction "1_1") (pintype "passive"))
      (node (ref "C36") (pin "1") (pinfunction "1_1") (pintype "passive"))
      (node (ref "C37") (pin "1") (pinfunction "1_1") (pintype "passive"))
      (node (ref "C38") (pin "1") (pinfunction "1_1") (pintype "passive"))
      (node (ref "C39") (pin "1") (pinfunction "1_1") (pintype "passive"))
      (node (ref "C4") (pin "1") (pinfunction "1_1") (pintype "passive"))
      (node (ref "C40") (pin "1") (pinfunction "1_1") (pintype "passive"))
      (node (ref "C5") (pin "1") (pinfunction "1_1") (pintype "passive"))
      (node (ref "C6") (pin "1") (pinfunction "1_1") (pintype "passive"))
      (node (ref "C7") (pin "1") (pinfunction "1_1") (pintype "passive"))
      (node (ref "C8") (pin "1") (pinfunction "1_1") (pintype "passive"))
      (node (ref "C9") (pin "1") (pinfunction "1_1") (pintype "passive"))
      (node (ref "D1") (pin "4") (pinfunction "VDD_4") (pintype "passive"))
      (node (ref "D10") (pin "4") (pinfunction "VDD_4") (pintype "passive"))
      (node (ref "D11") (pin "4") (pinfunction "VDD_4") (pintype "passive"))
      (node (ref "D12") (pin "4") (pinfunction "VDD_4") (pintype "passive"))
      (node (ref "D13") (pin "4") (pinfunction "VDD_4") (pintype "passive"))
      (node (ref "D14") (pin "4") (pinfunction "VDD_4") (pintype "passive"))
      (node (ref "D15") (pin "4") (pinfunction "VDD_4") (pintype "passive"))
      (node (ref "D16") (pin "4") (pinfunction "VDD_4") (pintype "passive"))
      (node (ref "D17") (pin "4") (pinfunction "VDD_4") (pintype "passive"))
      (node (ref "D18") (pin "4") (pinfunction "VDD_4") (pintype "passive"))
      (node (ref "D19") (pin "4") (pinfunction "VDD_4") (pintype "passive"))
      (node (ref "D2") (pin "4") (pinfunction "VDD_4") (pintype "passive"))
      (node (ref "D20") (pin "4") (pinfunction "VDD_4") (pintype "passive"))
      (node (ref "D21") (pin "4") (pinfunction "VDD_4") (pintype "passive"))
      (node (ref "D22") (pin "4") (pinfunction "VDD_4") (pintype "passive"))
      (node (ref "D23") (pin "4") (pinfunction "VDD_4") (pintype "passive"))
      (node (ref "D24") (pin "4") (pinfunction "VDD_4") (pintype "passive"))
      (node (ref "D25") (pin "4") (pinfunction "VDD_4") (pintype "passive"))
      (node (ref "D26") (pin "4") (pinfunction "VDD_4") (pintype "passive"))
      (node (ref "D27") (pin "4") (pinfunction "VDD_4") (pintype "passive"))
      (node (ref "D28") (pin "4") (pinfunction "VDD_4") (pintype "passive"))
      (node (ref "D29") (pin "4") (pinfunction "VDD_4") (pintype "passive"))
      (node (ref "D3") (pin "4") (pinfunction "VDD_4") (pintype "passive"))
      (node (ref "D30") (pin "4") (pinfunction "VDD_4") (pintype "passive"))
      (node (ref "D31") (pin "4") (pinfunction "VDD_4") (pintype "passive"))
      (node (ref "D32") (pin "4") (pinfunction "VDD_4") (pintype "passive"))
      (node (ref "D33") (pin "4") (pinfunction "VDD_4") (pintype "passive"))
      (node (ref "D34") (pin "4") (pinfunction "VDD_4") (pintype "passive"))
      (node (ref "D35") (pin "4") (pinfunction "VDD_4") (pintype "passive"))
      (node (ref "D36") (pin "4") (pinfunction "VDD_4") (pintype "passive"))
      (node (ref "D37") (pin "4") (pinfunction "VDD_4") (pintype "passive"))
      (node (ref "D38") (pin "4") (pinfunction "VDD_4") (pintype "passive"))
      (node (ref "D39") (pin "4") (pinfunction "VDD_4") (pintype "passive"))
      (node (ref "D4") (pin "4") (pinfunction "VDD_4") (pintype "passive"))
      (node (ref "D40") (pin "4") (pinfunction "VDD_4") (pintype "passive"))
      (node (ref "D5") (pin "4") (pinfunction "VDD_4") (pintype "passive"))
      (node (ref "D6") (pin "4") (pinfunction "VDD_4") (pintype "passive"))
      (node (ref "D7") (pin "4") (pinfunction "VDD_4") (pintype "passive"))
      (node (ref "D8") (pin "4") (pinfunction "VDD_4") (pintype "passive"))
      (node (ref "D9") (pin "4") (pinfunction "VDD_4") (pintype "passive"))
    )
  )
)
